# myduino_v1.net
KiCad netlist of a schematic drawn in EAGLE
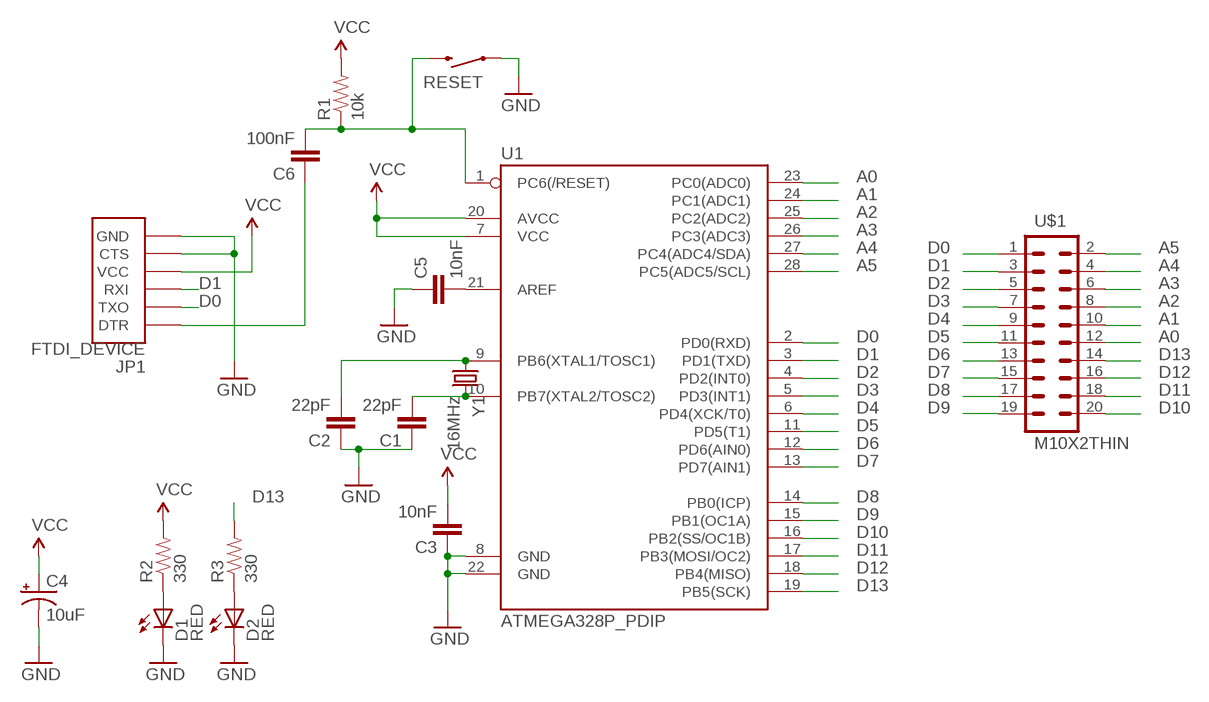
[diagram p0: schematic, sheet 1]

(export (version "E")
  (design (tool "Eeschema 10.0.6"))
  (components
    (comp (ref "C1")
      (value "22pF")
      (footprint "eagle-import:0402-CAP")
      (libsource (lib "eagle-import") (part "10NF-CER"))
    )
    (comp (ref "C2")
      (value "22pF")
      (footprint "eagle-import:0402-CAP")
      (libsource (lib "eagle-import") (part "10NF-CER"))
    )
    (comp (ref "C3")
      (value "10nF")
      (footprint "eagle-import:0402-CAP")
      (libsource (lib "eagle-import") (part "10NF-CER"))
    )
    (comp (ref "C4")
      (value "10uF")
      (footprint "eagle-import:EIA3216")
      (libsource (lib "eagle-import") (part "10UF-TANT"))
    )
    (comp (ref "C5")
      (value "10nF")
      (footprint "eagle-import:0402-CAP")
      (libsource (lib "eagle-import") (part "10NF-CER"))
    )
    (comp (ref "C6")
      (value "100nF")
      (footprint "eagle-import:0402-CAP")
      (libsource (lib "eagle-import") (part "10NF-CER"))
    )
    (comp (ref "D1")
      (value "RED")
      (footprint "eagle-import:LED-0603")
      (libsource (lib "eagle-import") (part "LED-RED0603"))
    )
    (comp (ref "D2")
      (value "RED")
      (footprint "eagle-import:LED-0603")
      (libsource (lib "eagle-import") (part "LED-RED0603"))
    )
    (comp (ref "JP1")
      (value "FTDI_DEVICE")
      (footprint "eagle-import:FTDI_DEVICE_SIDE")
      (libsource (lib "eagle-import") (part "FTDI_DEVICE"))
    )
    (comp (ref "R1")
      (value "10k")
      (footprint "eagle-import:0603-RES")
      (libsource (lib "eagle-import") (part "RESISTOR0603"))
    )
    (comp (ref "R2")
      (value "330")
      (footprint "eagle-import:0603-RES")
      (libsource (lib "eagle-import") (part "RESISTOR0603"))
    )
    (comp (ref "R3")
      (value "330")
      (footprint "eagle-import:0603-RES")
      (libsource (lib "eagle-import") (part "RESISTOR0603"))
    )
    (comp (ref "RESET")
      (value "SWITCH-MOMENTARY-2PTH")
      (footprint "eagle-import:TACTILE-PTH")
      (libsource (lib "eagle-import") (part "SWITCH-MOMENTARY-2PTH"))
    )
    (comp (ref "U$1")
      (value "M10X2THIN")
      (footprint "eagle-import:2X10_THIN")
      (libsource (lib "eagle-import") (part "M10X2THIN"))
    )
    (comp (ref "U1")
      (value "ATMEGA328P_PDIP")
      (footprint "eagle-import:DIL28-3")
      (libsource (lib "eagle-import") (part "ATMEGA328P_PDIP"))
    )
    (comp (ref "Y1")
      (value "16MHz")
      (footprint "eagle-import:HC49US")
      (libsource (lib "eagle-import") (part "CRYSTALHC49US"))
    )
  )
  (nets
    (net (code "1") (name "/A0") (class "Default")
      (node (ref "U$1") (pin "12") (pinfunction "12_12") (pintype "passive"))
      (node (ref "U1") (pin "23") (pinfunction "PC0(ADC0)_23") (pintype "bidirectional"))
    )
    (net (code "2") (name "/A1") (class "Default")
      (node (ref "U$1") (pin "10") (pinfunction "10_10") (pintype "passive"))
      (node (ref "U1") (pin "24") (pinfunction "PC1(ADC1)_24") (pintype "bidirectional"))
    )
    (net (code "3") (name "/A2") (class "Default")
      (node (ref "U$1") (pin "8") (pinfunction "8_8") (pintype "passive"))
      (node (ref "U1") (pin "25") (pinfunction "PC2(ADC2)_25") (pintype "bidirectional"))
    )
    (net (code "4") (name "/A3") (class "Default")
      (node (ref "U$1") (pin "6") (pinfunction "6_6") (pintype "passive"))
      (node (ref "U1") (pin "26") (pinfunction "PC3(ADC3)_26") (pintype "bidirectional"))
    )
    (net (code "5") (name "/A4") (class "Default")
      (node (ref "U$1") (pin "4") (pinfunction "4_4") (pintype "passive"))
      (node (ref "U1") (pin "27") (pinfunction "PC4(ADC4/SDA)_27") (pintype "bidirectional"))
    )
    (net (code "6") (name "/A5") (class "Default")
      (node (ref "U$1") (pin "2") (pinfunction "2_2") (pintype "passive"))
      (node (ref "U1") (pin "28") (pinfunction "PC5(ADC5/SCL)_28") (pintype "bidirectional"))
    )
    (net (code "7") (name "/D0") (class "Default")
      (node (ref "JP1") (pin "P$2") (pinfunction "TXO_P$2") (pintype "bidirectional"))
      (node (ref "U$1") (pin "1") (pinfunction "1_1") (pintype "passive"))
      (node (ref "U1") (pin "2") (pinfunction "PD0(RXD)_2") (pintype "bidirectional"))
    )
    (net (code "8") (name "/D1") (class "Default")
      (node (ref "JP1") (pin "P$3") (pinfunction "RXI_P$3") (pintype "bidirectional"))
      (node (ref "U$1") (pin "3") (pinfunction "3_3") (pintype "passive"))
      (node (ref "U1") (pin "3") (pinfunction "PD1(TXD)_3") (pintype "bidirectional"))
    )
    (net (code "9") (name "/D2") (class "Default")
      (node (ref "U$1") (pin "5") (pinfunction "5_5") (pintype "passive"))
      (node (ref "U1") (pin "4") (pinfunction "PD2(INT0)_4") (pintype "bidirectional"))
    )
    (net (code "10") (name "/D3") (class "Default")
      (node (ref "U$1") (pin "7") (pinfunction "7_7") (pintype "passive"))
      (node (ref "U1") (pin "5") (pinfunction "PD3(INT1)_5") (pintype "bidirectional"))
    )
    (net (code "11") (name "/D4") (class "Default")
      (node (ref "U$1") (pin "9") (pinfunction "9_9") (pintype "passive"))
      (node (ref "U1") (pin "6") (pinfunction "PD4(XCK/T0)_6") (pintype "bidirectional"))
    )
    (net (code "12") (name "/D5") (class "Default")
      (node (ref "U$1") (pin "11") (pinfunction "11_11") (pintype "passive"))
      (node (ref "U1") (pin "11") (pinfunction "PD5(T1)_11") (pintype "bidirectional"))
    )
    (net (code "13") (name "/D6") (class "Default")
      (node (ref "U$1") (pin "13") (pinfunction "13_13") (pintype "passive"))
      (node (ref "U1") (pin "12") (pinfunction "PD6(AIN0)_12") (pintype "bidirectional"))
    )
    (net (code "14") (name "/D7") (class "Default")
      (node (ref "U$1") (pin "15") (pinfunction "15_15") (pintype "passive"))
      (node (ref "U1") (pin "13") (pinfunction "PD7(AIN1)_13") (pintype "bidirectional"))
    )
    (net (code "15") (name "/D8") (class "Default")
      (node (ref "U$1") (pin "17") (pinfunction "17_17") (pintype "passive"))
      (node (ref "U1") (pin "14") (pinfunction "PB0(ICP)_14") (pintype "bidirectional"))
    )
    (net (code "16") (name "/D9") (class "Default")
      (node (ref "U$1") (pin "19") (pinfunction "19_19") (pintype "passive"))
      (node (ref "U1") (pin "15") (pinfunction "PB1(OC1A)_15") (pintype "bidirectional"))
    )
    (net (code "17") (name "/D10") (class "Default")
      (node (ref "U$1") (pin "20") (pinfunction "20_20") (pintype "passive"))
      (node (ref "U1") (pin "16") (pinfunction "PB2(SS/OC1B)_16") (pintype "bidirectional"))
    )
    (net (code "18") (name "/D11") (class "Default")
      (node (ref "U$1") (pin "18") (pinfunction "18_18") (pintype "passive"))
      (node (ref "U1") (pin "17") (pinfunction "PB3(MOSI/OC2)_17") (pintype "bidirectional"))
    )
    (net (code "19") (name "/D12") (class "Default")
      (node (ref "U$1") (pin "16") (pinfunction "16_16") (pintype "passive"))
      (node (ref "U1") (pin "18") (pinfunction "PB4(MISO)_18") (pintype "bidirectional"))
    )
    (net (code "20") (name "/D13") (class "Default")
      (node (ref "R3") (pin "2") (pinfunction "2_2") (pintype "passive"))
      (node (ref "U$1") (pin "14") (pinfunction "14_14") (pintype "passive"))
      (node (ref "U1") (pin "19") (pinfunction "PB5(SCK)_19") (pintype "bidirectional"))
    )
    (net (code "21") (name "GND") (class "Default")
      (node (ref "C1") (pin "1") (pinfunction "1_1") (pintype "passive"))
      (node (ref "C2") (pin "1") (pinfunction "1_1") (pintype "passive"))
      (node (ref "C3") (pin "1") (pinfunction "1_1") (pintype "passive"))
      (node (ref "C4") (pin "C") (pinfunction "-_C") (pintype "passive"))
      (node (ref "C5") (pin "1") (pinfunction "1_1") (pintype "passive"))
      (node (ref "D1") (pin "C") (pinfunction "C_C") (pintype "passive"))
      (node (ref "D2") (pin "C") (pinfunction "C_C") (pintype "passive"))
      (node (ref "JP1") (pin "P$5") (pinfunction "CTS_P$5") (pintype "bidirectional"))
      (node (ref "JP1") (pin "P$6") (pinfunction "GND_P$6") (pintype "bidirectional"))
      (node (ref "RESET") (pin "1") (pinfunction "1_1") (pintype "passive"))
      (node (ref "U1") (pin "22") (pinfunction "GND_22") (pintype "bidirectional"))
      (node (ref "U1") (pin "8") (pinfunction "GND_8") (pintype "bidirectional"))
    )
    (net (code "22") (name "Net-(D1-PadA)") (class "Default")
      (node (ref "D1") (pin "A") (pinfunction "A_A") (pintype "passive"))
      (node (ref "R2") (pin "1") (pinfunction "1_1") (pintype "passive"))
    )
    (net (code "23") (name "Net-(D2-PadA)") (class "Default")
      (node (ref "D2") (pin "A") (pinfunction "A_A") (pintype "passive"))
      (node (ref "R3") (pin "1") (pinfunction "1_1") (pintype "passive"))
    )
    (net (code "24") (name "Net-(JP1-DTR)") (class "Default")
      (node (ref "C6") (pin "1") (pinfunction "1_1") (pintype "passive"))
      (node (ref "JP1") (pin "P$1") (pinfunction "DTR_P$1") (pintype "bidirectional"))
    )
    (net (code "25") (name "Net-(RESET-2)") (class "Default")
      (node (ref "C6") (pin "2") (pinfunction "2_2") (pintype "passive"))
      (node (ref "R1") (pin "1") (pinfunction "1_1") (pintype "passive"))
      (node (ref "RESET") (pin "3") (pinfunction "2_3") (pintype "passive"))
      (node (ref "U1") (pin "1") (pinfunction "PC6(/RESET)_1") (pintype "bidirectional"))
    )
    (net (code "26") (name "Net-(U1-AREF)") (class "Default")
      (node (ref "C5") (pin "2") (pinfunction "2_2") (pintype "passive"))
      (node (ref "U1") (pin "21") (pinfunction "AREF_21") (pintype "bidirectional"))
    )
    (net (code "27") (name "Net-(U1-PB6(XTAL1{slash}TOSC1))") (class "Default")
      (node (ref "C2") (pin "2") (pinfunction "2_2") (pintype "passive"))
      (node (ref "U1") (pin "9") (pinfunction "PB6(XTAL1/TOSC1)_9") (pintype "bidirectional"))
      (node (ref "Y1") (pin "1") (pinfunction "1_1") (pintype "passive"))
    )
    (net (code "28") (name "Net-(U1-PB7(XTAL2{slash}TOSC2))") (class "Default")
      (node (ref "C1") (pin "2") (pinfunction "2_2") (pintype "passive"))
      (node (ref "U1") (pin "10") (pinfunction "PB7(XTAL2/TOSC2)_10") (pintype "bidirectional"))
      (node (ref "Y1") (pin "2") (pinfunction "2_2") (pintype "passive"))
    )
    (net (code "29") (name "VCC") (class "Default")
      (node (ref "C3") (pin "2") (pinfunction "2_2") (pintype "passive"))
      (node (ref "C4") (pin "A") (pinfunction "+_A") (pintype "passive"))
      (node (ref "JP1") (pin "P$4") (pinfunction "VCC_P$4") (pintype "bidirectional"))
      (node (ref "R1") (pin "2") (pinfunction "2_2") (pintype "passive"))
      (node (ref "R2") (pin "2") (pinfunction "2_2") (pintype "passive"))
      (node (ref "U1") (pin "20") (pinfunction "AVCC_20") (pintype "bidirectional"))
      (node (ref "U1") (pin "7") (pinfunction "VCC_7") (pintype "bidirectional"))
    )
  )
)
